# 51.net
KiCad netlist of a schematic drawn in EasyEDA Pro
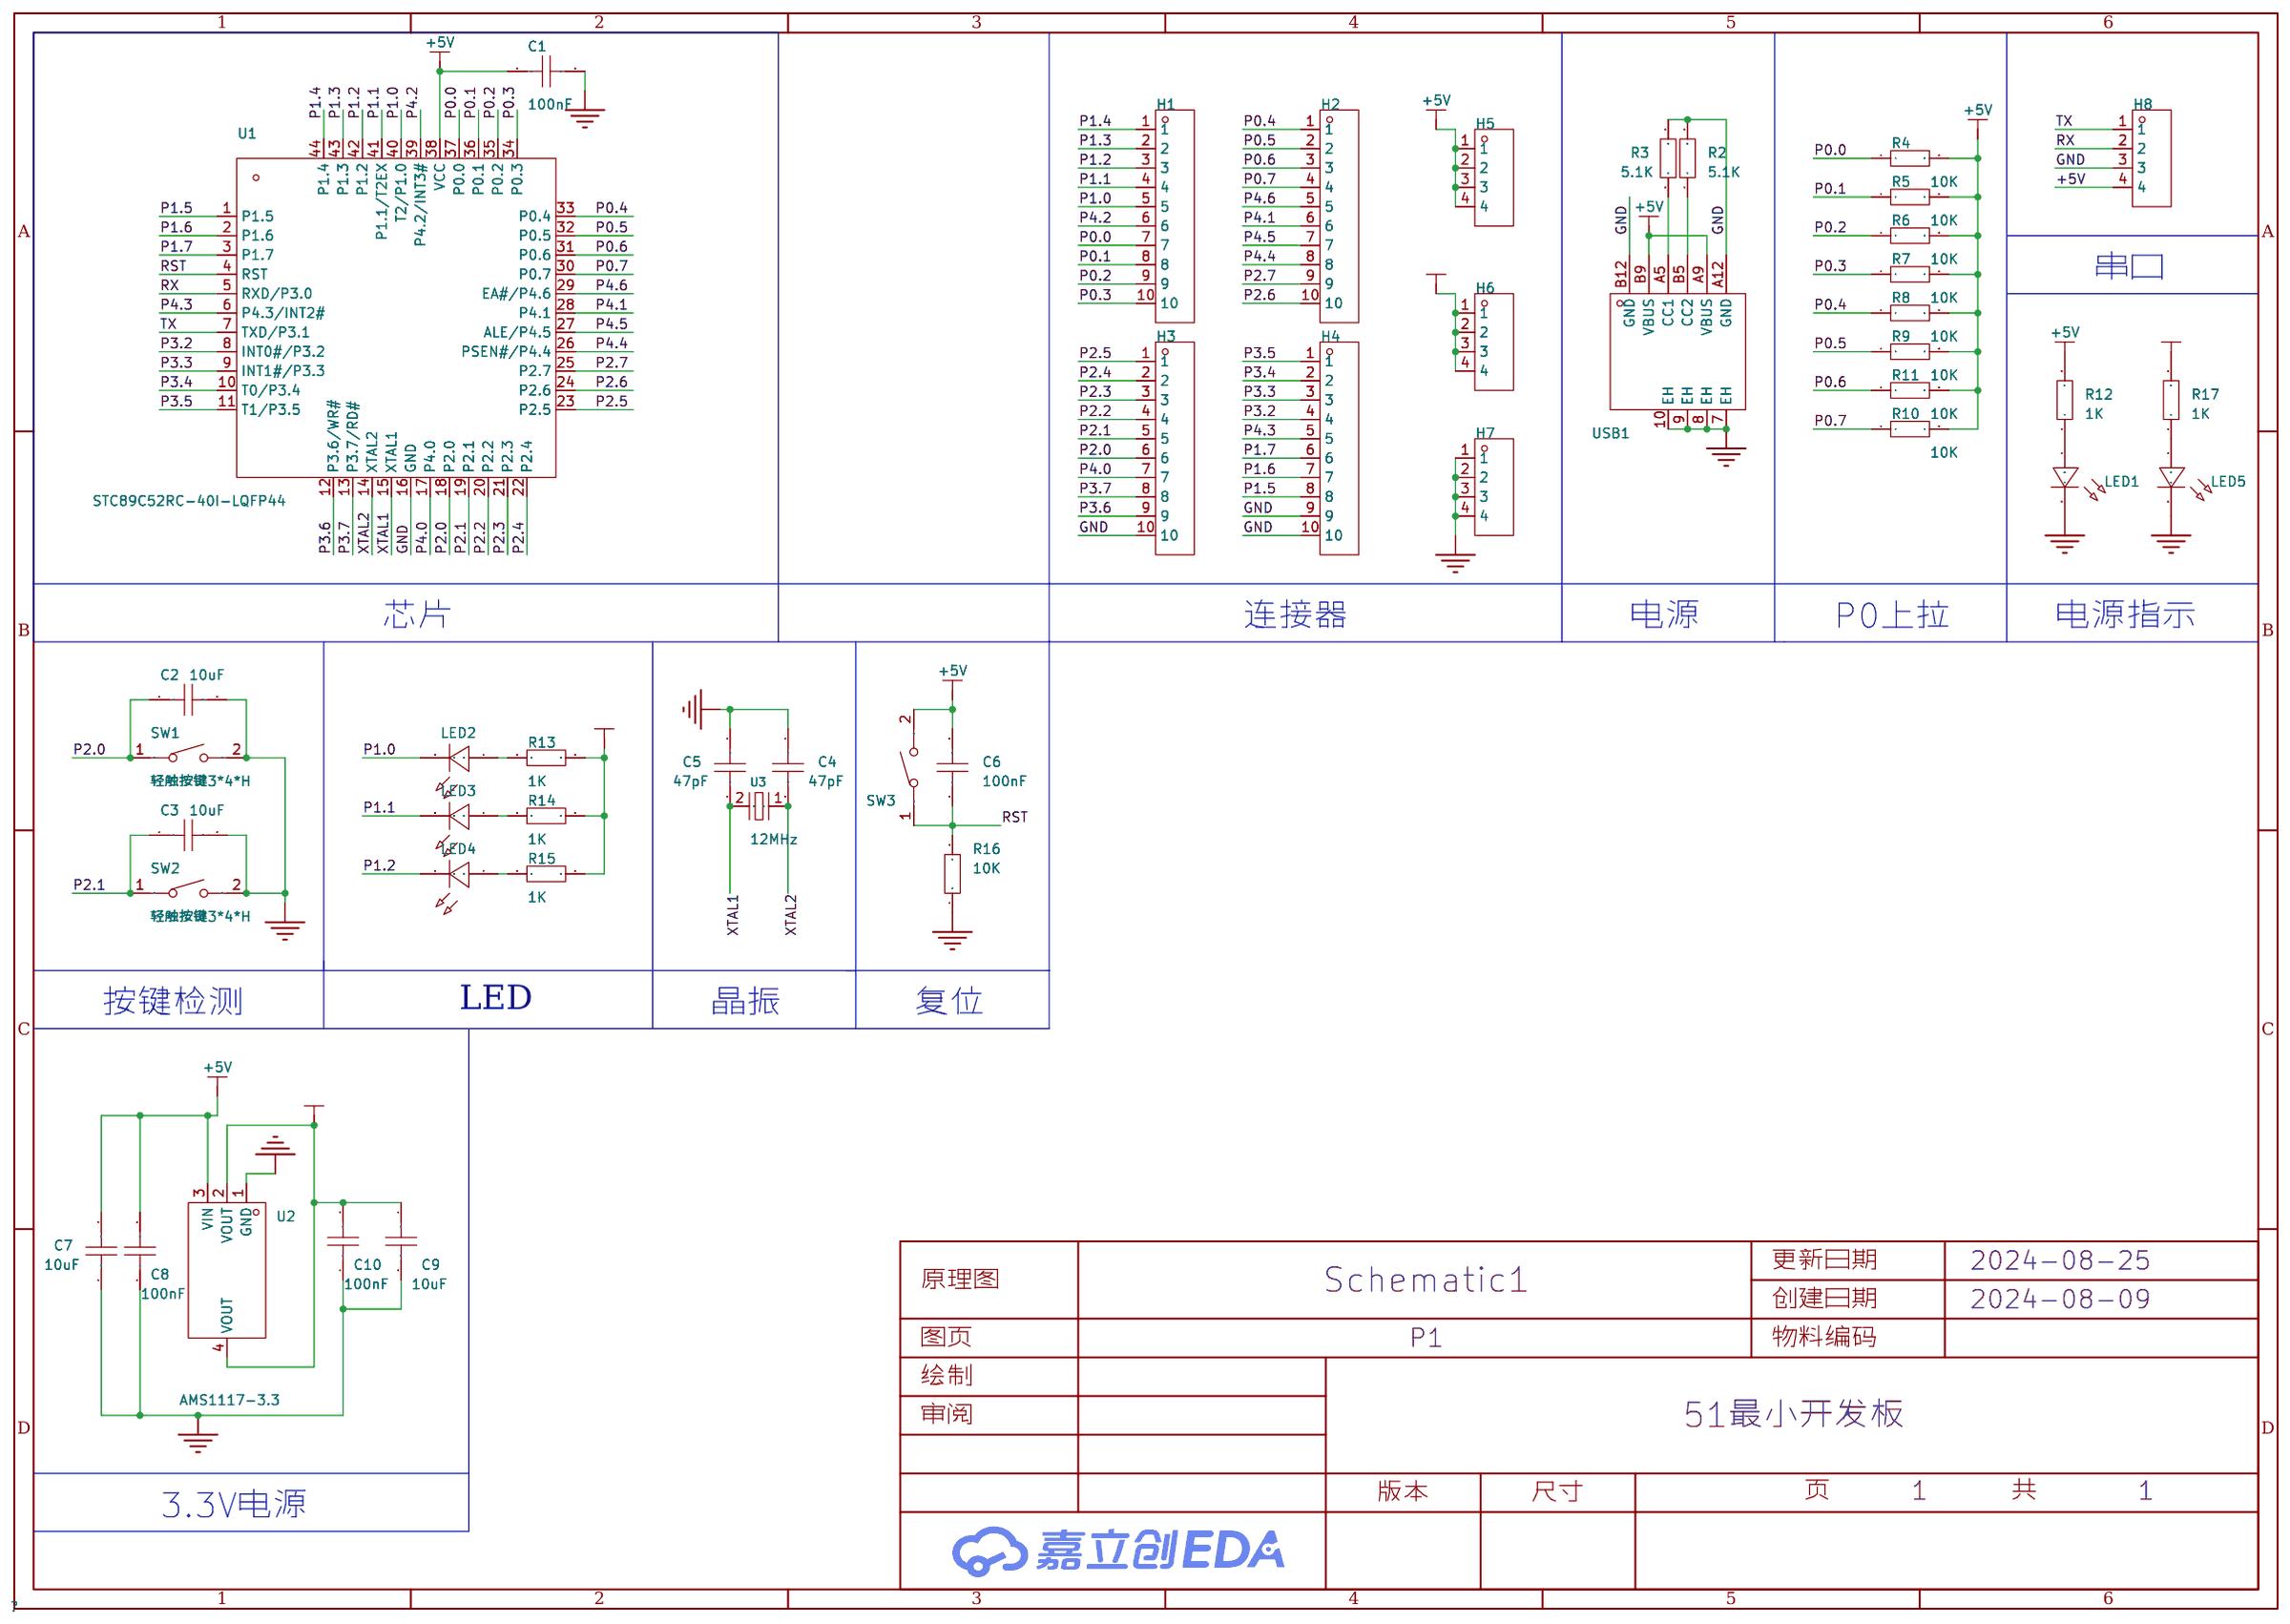
[diagram p0: schematic sheet]

(export (version "E")
  (design (tool "Eeschema 10.0.6"))
  (components
    (comp (ref "C1")
      (value "100nF")
      (footprint "easyedapro:C0603")
      (libsource (lib "easyedapro") (part "CapAcitance"))
    )
    (comp (ref "C2")
      (value "10uF")
      (footprint "easyedapro:C0603")
      (libsource (lib "easyedapro") (part "CapAcitance"))
    )
    (comp (ref "C3")
      (value "10uF")
      (footprint "easyedapro:C0603")
      (libsource (lib "easyedapro") (part "CapAcitance"))
    )
    (comp (ref "C4")
      (value "47pF")
      (footprint "easyedapro:C0603")
      (libsource (lib "easyedapro") (part "CapAcitance"))
    )
    (comp (ref "C5")
      (value "47pF")
      (footprint "easyedapro:C0603")
      (libsource (lib "easyedapro") (part "CapAcitance"))
    )
    (comp (ref "C6")
      (value "100nF")
      (footprint "easyedapro:C0603")
      (libsource (lib "easyedapro") (part "CapAcitance"))
    )
    (comp (ref "C7")
      (value "10uF")
      (footprint "easyedapro:C0603")
      (libsource (lib "easyedapro") (part "CapAcitance"))
    )
    (comp (ref "C8")
      (value "100nF")
      (footprint "easyedapro:C0603")
      (libsource (lib "easyedapro") (part "CapAcitance"))
    )
    (comp (ref "C9")
      (value "10uF")
      (footprint "easyedapro:C0603")
      (libsource (lib "easyedapro") (part "CapAcitance"))
    )
    (comp (ref "C10")
      (value "100nF")
      (footprint "easyedapro:C0603")
      (libsource (lib "easyedapro") (part "CapAcitance"))
    )
    (comp (ref "H1")
      (value "~")
      (footprint "easyedapro:HDR-TH_10P-P2.54-V-F")
      (libsource (lib "easyedapro") (part "X5511FV-10-C70D30-1000"))
    )
    (comp (ref "H2")
      (value "~")
      (footprint "easyedapro:HDR-TH_10P-P2.54-V-F")
      (libsource (lib "easyedapro") (part "X5511FV-10-C70D30-1000"))
    )
    (comp (ref "H3")
      (value "~")
      (footprint "easyedapro:HDR-TH_10P-P2.54-V-F")
      (libsource (lib "easyedapro") (part "X5511FV-10-C70D30-1000"))
    )
    (comp (ref "H4")
      (value "~")
      (footprint "easyedapro:HDR-TH_10P-P2.54-V-F")
      (libsource (lib "easyedapro") (part "X5511FV-10-C70D30-1000"))
    )
    (comp (ref "H5")
      (value "~")
      (footprint "easyedapro:HDR-TH_4P-P2.54-V-F")
      (libsource (lib "easyedapro") (part "2.54-1*4P母"))
    )
    (comp (ref "H6")
      (value "~")
      (footprint "easyedapro:HDR-TH_4P-P2.54-V-F")
      (libsource (lib "easyedapro") (part "2.54-1*4P母"))
    )
    (comp (ref "H7")
      (value "~")
      (footprint "easyedapro:HDR-TH_4P-P2.54-V-F")
      (libsource (lib "easyedapro") (part "2.54-1*4P母"))
    )
    (comp (ref "H8")
      (value "~")
      (footprint "easyedapro:HDR-TH_4P-P2.54-V-M")
      (libsource (lib "easyedapro") (part "PZ254V-11-04P"))
    )
    (comp (ref "LED1")
      (value "~")
      (footprint "easyedapro:LED_TH-3mm")
      (libsource (lib "easyedapro") (part "LED_TH-R"))
    )
    (comp (ref "LED2")
      (value "~")
      (footprint "easyedapro:LED_TH-3mm")
      (libsource (lib "easyedapro") (part "LED_TH-R"))
    )
    (comp (ref "LED3")
      (value "~")
      (footprint "easyedapro:LED_TH-3mm")
      (libsource (lib "easyedapro") (part "LED_TH-R"))
    )
    (comp (ref "LED4")
      (value "~")
      (footprint "easyedapro:LED_TH-3mm")
      (libsource (lib "easyedapro") (part "LED_TH-R"))
    )
    (comp (ref "LED5")
      (value "~")
      (footprint "easyedapro:LED_TH-3mm")
      (libsource (lib "easyedapro") (part "LED_TH-R"))
    )
    (comp (ref "R2") (value "5.1K") (footprint "easyedapro:R0603") (libsource (lib "easyedapro") (part "电阻")))
    (comp (ref "R3") (value "5.1K") (footprint "easyedapro:R0603") (libsource (lib "easyedapro") (part "电阻")))
    (comp (ref "R4") (value "10K") (footprint "easyedapro:R0603") (libsource (lib "easyedapro") (part "电阻")))
    (comp (ref "R5") (value "10K") (footprint "easyedapro:R0603") (libsource (lib "easyedapro") (part "电阻")))
    (comp (ref "R6") (value "10K") (footprint "easyedapro:R0603") (libsource (lib "easyedapro") (part "电阻")))
    (comp (ref "R7") (value "10K") (footprint "easyedapro:R0603") (libsource (lib "easyedapro") (part "电阻")))
    (comp (ref "R8") (value "10K") (footprint "easyedapro:R0603") (libsource (lib "easyedapro") (part "电阻")))
    (comp (ref "R9") (value "10K") (footprint "easyedapro:R0603") (libsource (lib "easyedapro") (part "电阻")))
    (comp (ref "R10") (value "10K") (footprint "easyedapro:R0603") (libsource (lib "easyedapro") (part "电阻")))
    (comp (ref "R11") (value "10K") (footprint "easyedapro:R0603") (libsource (lib "easyedapro") (part "电阻")))
    (comp (ref "R12") (value "1K") (footprint "easyedapro:R0603") (libsource (lib "easyedapro") (part "电阻")))
    (comp (ref "R13") (value "1K") (footprint "easyedapro:R0603") (libsource (lib "easyedapro") (part "电阻")))
    (comp (ref "R14") (value "1K") (footprint "easyedapro:R0603") (libsource (lib "easyedapro") (part "电阻")))
    (comp (ref "R15") (value "1K") (footprint "easyedapro:R0603") (libsource (lib "easyedapro") (part "电阻")))
    (comp (ref "R16") (value "10K") (footprint "easyedapro:R0603") (libsource (lib "easyedapro") (part "电阻")))
    (comp (ref "R17") (value "1K") (footprint "easyedapro:R0603") (libsource (lib "easyedapro") (part "电阻")))
    (comp (ref "SW1")
      (value "轻触按键3*4*H")
      (footprint "easyedapro:SW-SMD_L4.0-W2.9-LS5.0")
      (libsource (lib "easyedapro") (part "轻触按键3*4*H"))
    )
    (comp (ref "SW2")
      (value "轻触按键3*4*H")
      (footprint "easyedapro:SW-SMD_L4.0-W2.9-LS5.0")
      (libsource (lib "easyedapro") (part "轻触按键3*4*H"))
    )
    (comp (ref "SW3")
      (value "轻触按键3*4*H")
      (footprint "easyedapro:SW-SMD_L4.0-W2.9-LS5.0")
      (libsource (lib "easyedapro") (part "轻触按键3*4*H"))
    )
    (comp (ref "U1")
      (value "STC89C52RC-40I-LQFP44")
      (footprint "easyedapro:LQFP-44_L10.0-W10.0-P0.80-LS12.0-BL")
      (description "CPU内核:51系列;程序存储容量:8KB;RAM总容量:512Byte;GPIO端口数量:39;工作电压范围:3.3V~5.5V;CPU最大主频:-;程序存储器类型:FLASH;")
      (fields (field (name "Manufacturer") "STC(宏晶)"))
      (libsource (lib "easyedapro") (part "STC89C52RC-40I_C8707"))
    )
    (comp (ref "U2")
      (value "AMS1117-3.3")
      (footprint "easyedapro:SOT-223-3_L6.5-W3.4-P2.30-LS7.0-BR")
      (description "输出类型:固定;最大输入电压:-;输出电压:3.3V;最大输出电流:1A;电源纹波抑制比(PSRR):72dB@(120Hz);输出极性:正极;")
      (fields (field (name "Manufacturer") "AMS"))
      (libsource (lib "easyedapro") (part "AMS1117-3.3"))
    )
    (comp (ref "U3")
      (value "12MHz")
      (footprint "easyedapro:CRYSTAL-SMD_L11.4-W4.7-LS12.7")
      (description "频率:12MHz;常温频差:±30ppm;外接负载电容:18pF;频率稳定度(全温):±35ppm;")
      (fields
        (field (name "Manufacturer Part") "ABLS-12.000MHZ-B4H-T")
        (field (name "Manufacturer") "ABRACON")
      )
      (libsource (lib "easyedapro") (part "ABLS-12.000MHZ-B4H-T"))
    )
    (comp (ref "USB1")
      (value "~")
      (footprint "easyedapro:USB_ TYPE-C-6P")
      (libsource (lib "easyedapro") (part "USB_ TYPE-C-6P"))
    )
  )
  (nets
    (net (code "1") (name "+5V") (class "Default")
      (node (ref "C1") (pin "1") (pinfunction "1_1") (pintype "input"))
      (node (ref "C6") (pin "2") (pinfunction "2_2") (pintype "input"))
      (node (ref "C7") (pin "1") (pinfunction "1_1") (pintype "input"))
      (node (ref "C8") (pin "2") (pinfunction "2_2") (pintype "input"))
      (node (ref "H5") (pin "1") (pinfunction "1_1") (pintype "unspecified"))
      (node (ref "H5") (pin "2") (pinfunction "2_2") (pintype "unspecified"))
      (node (ref "H5") (pin "3") (pinfunction "3_3") (pintype "unspecified"))
      (node (ref "H5") (pin "4") (pinfunction "4_4") (pintype "unspecified"))
      (node (ref "H8") (pin "4") (pinfunction "4_4") (pintype "unspecified"))
      (node (ref "R10") (pin "2") (pinfunction "2_2") (pintype "input"))
      (node (ref "R11") (pin "2") (pinfunction "2_2") (pintype "input"))
      (node (ref "R12") (pin "2") (pinfunction "2_2") (pintype "input"))
      (node (ref "R4") (pin "2") (pinfunction "2_2") (pintype "input"))
      (node (ref "R5") (pin "2") (pinfunction "2_2") (pintype "input"))
      (node (ref "R6") (pin "2") (pinfunction "2_2") (pintype "input"))
      (node (ref "R7") (pin "2") (pinfunction "2_2") (pintype "input"))
      (node (ref "R8") (pin "2") (pinfunction "2_2") (pintype "input"))
      (node (ref "R9") (pin "2") (pinfunction "2_2") (pintype "input"))
      (node (ref "SW3") (pin "2") (pinfunction "2_2") (pintype "unspecified"))
      (node (ref "U1") (pin "38") (pinfunction "VCC_38") (pintype "unspecified"))
      (node (ref "U2") (pin "3") (pinfunction "VIN_3") (pintype "unspecified"))
      (node (ref "USB1") (pin "A9") (pinfunction "VBUS_A9") (pintype "input"))
      (node (ref "USB1") (pin "B9") (pinfunction "VBUS_B9") (pintype "input"))
    )
    (net (code "2") (name "/P0.0") (class "Default")
      (node (ref "H1") (pin "7") (pinfunction "7_7") (pintype "unspecified"))
      (node (ref "R4") (pin "1") (pinfunction "1_1") (pintype "input"))
      (node (ref "U1") (pin "37") (pinfunction "P0.0_37") (pintype "unspecified"))
    )
    (net (code "3") (name "/P0.1") (class "Default")
      (node (ref "H1") (pin "8") (pinfunction "8_8") (pintype "unspecified"))
      (node (ref "R5") (pin "1") (pinfunction "1_1") (pintype "input"))
      (node (ref "U1") (pin "36") (pinfunction "P0.1_36") (pintype "unspecified"))
    )
    (net (code "4") (name "/P0.2") (class "Default")
      (node (ref "H1") (pin "9") (pinfunction "9_9") (pintype "unspecified"))
      (node (ref "R6") (pin "1") (pinfunction "1_1") (pintype "input"))
      (node (ref "U1") (pin "35") (pinfunction "P0.2_35") (pintype "unspecified"))
    )
    (net (code "5") (name "/P0.3") (class "Default")
      (node (ref "H1") (pin "10") (pinfunction "10_10") (pintype "unspecified"))
      (node (ref "R7") (pin "1") (pinfunction "1_1") (pintype "input"))
      (node (ref "U1") (pin "34") (pinfunction "P0.3_34") (pintype "unspecified"))
    )
    (net (code "6") (name "/P0.4") (class "Default")
      (node (ref "H2") (pin "1") (pinfunction "1_1") (pintype "unspecified"))
      (node (ref "R8") (pin "1") (pinfunction "1_1") (pintype "input"))
      (node (ref "U1") (pin "33") (pinfunction "P0.4_33") (pintype "unspecified"))
    )
    (net (code "7") (name "/P0.5") (class "Default")
      (node (ref "H2") (pin "2") (pinfunction "2_2") (pintype "unspecified"))
      (node (ref "R9") (pin "1") (pinfunction "1_1") (pintype "input"))
      (node (ref "U1") (pin "32") (pinfunction "P0.5_32") (pintype "unspecified"))
    )
    (net (code "8") (name "/P0.6") (class "Default")
      (node (ref "H2") (pin "3") (pinfunction "3_3") (pintype "unspecified"))
      (node (ref "R11") (pin "1") (pinfunction "1_1") (pintype "input"))
      (node (ref "U1") (pin "31") (pinfunction "P0.6_31") (pintype "unspecified"))
    )
    (net (code "9") (name "/P0.7") (class "Default")
      (node (ref "H2") (pin "4") (pinfunction "4_4") (pintype "unspecified"))
      (node (ref "R10") (pin "1") (pinfunction "1_1") (pintype "input"))
      (node (ref "U1") (pin "30") (pinfunction "P0.7_30") (pintype "unspecified"))
    )
    (net (code "10") (name "/P1.0") (class "Default")
      (node (ref "H1") (pin "5") (pinfunction "5_5") (pintype "unspecified"))
      (node (ref "LED2") (pin "2") (pinfunction "A_2") (pintype "input"))
      (node (ref "U1") (pin "40") (pinfunction "T2/P1.0_40") (pintype "unspecified"))
    )
    (net (code "11") (name "/P1.1") (class "Default")
      (node (ref "H1") (pin "4") (pinfunction "4_4") (pintype "unspecified"))
      (node (ref "LED3") (pin "2") (pinfunction "A_2") (pintype "input"))
      (node (ref "U1") (pin "41") (pinfunction "P1.1/T2EX_41") (pintype "unspecified"))
    )
    (net (code "12") (name "/P1.2") (class "Default")
      (node (ref "H1") (pin "3") (pinfunction "3_3") (pintype "unspecified"))
      (node (ref "LED4") (pin "2") (pinfunction "A_2") (pintype "input"))
      (node (ref "U1") (pin "42") (pinfunction "P1.2_42") (pintype "unspecified"))
    )
    (net (code "13") (name "/P1.3") (class "Default")
      (node (ref "H1") (pin "2") (pinfunction "2_2") (pintype "unspecified"))
      (node (ref "U1") (pin "43") (pinfunction "P1.3_43") (pintype "unspecified"))
    )
    (net (code "14") (name "/P1.4") (class "Default")
      (node (ref "H1") (pin "1") (pinfunction "1_1") (pintype "unspecified"))
      (node (ref "U1") (pin "44") (pinfunction "P1.4_44") (pintype "unspecified"))
    )
    (net (code "15") (name "/P1.5") (class "Default")
      (node (ref "H4") (pin "8") (pinfunction "8_8") (pintype "unspecified"))
      (node (ref "U1") (pin "1") (pinfunction "P1.5_1") (pintype "unspecified"))
    )
    (net (code "16") (name "/P1.6") (class "Default")
      (node (ref "H4") (pin "7") (pinfunction "7_7") (pintype "unspecified"))
      (node (ref "U1") (pin "2") (pinfunction "P1.6_2") (pintype "unspecified"))
    )
    (net (code "17") (name "/P1.7") (class "Default")
      (node (ref "H4") (pin "6") (pinfunction "6_6") (pintype "unspecified"))
      (node (ref "U1") (pin "3") (pinfunction "P1.7_3") (pintype "unspecified"))
    )
    (net (code "18") (name "/P2.0") (class "Default")
      (node (ref "C2") (pin "1") (pinfunction "1_1") (pintype "input"))
      (node (ref "H3") (pin "6") (pinfunction "6_6") (pintype "unspecified"))
      (node (ref "SW1") (pin "1") (pinfunction "1_1") (pintype "unspecified"))
      (node (ref "U1") (pin "18") (pinfunction "P2.0_18") (pintype "unspecified"))
    )
    (net (code "19") (name "/P2.1") (class "Default")
      (node (ref "C3") (pin "1") (pinfunction "1_1") (pintype "input"))
      (node (ref "H3") (pin "5") (pinfunction "5_5") (pintype "unspecified"))
      (node (ref "SW2") (pin "1") (pinfunction "1_1") (pintype "unspecified"))
      (node (ref "U1") (pin "19") (pinfunction "P2.1_19") (pintype "unspecified"))
    )
    (net (code "20") (name "/P2.2") (class "Default")
      (node (ref "H3") (pin "4") (pinfunction "4_4") (pintype "unspecified"))
      (node (ref "U1") (pin "20") (pinfunction "P2.2_20") (pintype "unspecified"))
    )
    (net (code "21") (name "/P2.3") (class "Default")
      (node (ref "H3") (pin "3") (pinfunction "3_3") (pintype "unspecified"))
      (node (ref "U1") (pin "21") (pinfunction "P2.3_21") (pintype "unspecified"))
    )
    (net (code "22") (name "/P2.4") (class "Default")
      (node (ref "H3") (pin "2") (pinfunction "2_2") (pintype "unspecified"))
      (node (ref "U1") (pin "22") (pinfunction "P2.4_22") (pintype "unspecified"))
    )
    (net (code "23") (name "/P2.5") (class "Default")
      (node (ref "H3") (pin "1") (pinfunction "1_1") (pintype "unspecified"))
      (node (ref "U1") (pin "23") (pinfunction "P2.5_23") (pintype "unspecified"))
    )
    (net (code "24") (name "/P2.6") (class "Default")
      (node (ref "H2") (pin "10") (pinfunction "10_10") (pintype "unspecified"))
      (node (ref "U1") (pin "24") (pinfunction "P2.6_24") (pintype "unspecified"))
    )
    (net (code "25") (name "/P2.7") (class "Default")
      (node (ref "H2") (pin "9") (pinfunction "9_9") (pintype "unspecified"))
      (node (ref "U1") (pin "25") (pinfunction "P2.7_25") (pintype "unspecified"))
    )
    (net (code "26") (name "/P3.2") (class "Default")
      (node (ref "H4") (pin "4") (pinfunction "4_4") (pintype "unspecified"))
      (node (ref "U1") (pin "8") (pinfunction "INT0#/P3.2_8") (pintype "unspecified"))
    )
    (net (code "27") (name "/P3.3") (class "Default")
      (node (ref "H4") (pin "3") (pinfunction "3_3") (pintype "unspecified"))
      (node (ref "U1") (pin "9") (pinfunction "INT1#/P3.3_9") (pintype "unspecified"))
    )
    (net (code "28") (name "/P3.4") (class "Default")
      (node (ref "H4") (pin "2") (pinfunction "2_2") (pintype "unspecified"))
      (node (ref "U1") (pin "10") (pinfunction "T0/P3.4_10") (pintype "unspecified"))
    )
    (net (code "29") (name "/P3.5") (class "Default")
      (node (ref "H4") (pin "1") (pinfunction "1_1") (pintype "unspecified"))
      (node (ref "U1") (pin "11") (pinfunction "T1/P3.5_11") (pintype "unspecified"))
    )
    (net (code "30") (name "/P3.6") (class "Default")
      (node (ref "H3") (pin "9") (pinfunction "9_9") (pintype "unspecified"))
      (node (ref "U1") (pin "12") (pinfunction "P3.6/WR#_12") (pintype "unspecified"))
    )
    (net (code "31") (name "/P3.7") (class "Default")
      (node (ref "H3") (pin "8") (pinfunction "8_8") (pintype "unspecified"))
      (node (ref "U1") (pin "13") (pinfunction "P3.7/RD#_13") (pintype "unspecified"))
    )
    (net (code "32") (name "/P4.0") (class "Default")
      (node (ref "H3") (pin "7") (pinfunction "7_7") (pintype "unspecified"))
      (node (ref "U1") (pin "17") (pinfunction "P4.0_17") (pintype "unspecified"))
    )
    (net (code "33") (name "/P4.1") (class "Default")
      (node (ref "H2") (pin "6") (pinfunction "6_6") (pintype "unspecified"))
      (node (ref "U1") (pin "28") (pinfunction "P4.1_28") (pintype "unspecified"))
    )
    (net (code "34") (name "/P4.2") (class "Default")
      (node (ref "H1") (pin "6") (pinfunction "6_6") (pintype "unspecified"))
      (node (ref "U1") (pin "39") (pinfunction "P4.2/INT3#_39") (pintype "unspecified"))
    )
    (net (code "35") (name "/P4.3") (class "Default")
      (node (ref "H4") (pin "5") (pinfunction "5_5") (pintype "unspecified"))
      (node (ref "U1") (pin "6") (pinfunction "P4.3/INT2#_6") (pintype "unspecified"))
    )
    (net (code "36") (name "/P4.4") (class "Default")
      (node (ref "H2") (pin "8") (pinfunction "8_8") (pintype "unspecified"))
      (node (ref "U1") (pin "26") (pinfunction "PSEN#/P4.4_26") (pintype "unspecified"))
    )
    (net (code "37") (name "/P4.5") (class "Default")
      (node (ref "H2") (pin "7") (pinfunction "7_7") (pintype "unspecified"))
      (node (ref "U1") (pin "27") (pinfunction "ALE/P4.5_27") (pintype "unspecified"))
    )
    (net (code "38") (name "/P4.6") (class "Default")
      (node (ref "H2") (pin "5") (pinfunction "5_5") (pintype "unspecified"))
      (node (ref "U1") (pin "29") (pinfunction "EA#/P4.6_29") (pintype "unspecified"))
    )
    (net (code "39") (name "/RST") (class "Default")
      (node (ref "C6") (pin "1") (pinfunction "1_1") (pintype "input"))
      (node (ref "R16") (pin "2") (pinfunction "2_2") (pintype "input"))
      (node (ref "SW3") (pin "1") (pinfunction "1_1") (pintype "unspecified"))
      (node (ref "U1") (pin "4") (pinfunction "RST_4") (pintype "unspecified"))
    )
    (net (code "40") (name "/RX") (class "Default")
      (node (ref "H8") (pin "2") (pinfunction "2_2") (pintype "unspecified"))
      (node (ref "U1") (pin "5") (pinfunction "RXD/P3.0_5") (pintype "unspecified"))
    )
    (net (code "41") (name "/TX") (class "Default")
      (node (ref "H8") (pin "1") (pinfunction "1_1") (pintype "unspecified"))
      (node (ref "U1") (pin "7") (pinfunction "TXD/P3.1_7") (pintype "unspecified"))
    )
    (net (code "42") (name "/XTAL1") (class "Default")
      (node (ref "C5") (pin "2") (pinfunction "2_2") (pintype "input"))
      (node (ref "U1") (pin "15") (pinfunction "XTAL1_15") (pintype "unspecified"))
      (node (ref "U3") (pin "2") (pinfunction "GND_2") (pintype "input"))
    )
    (net (code "43") (name "/XTAL2") (class "Default")
      (node (ref "C4") (pin "2") (pinfunction "2_2") (pintype "input"))
      (node (ref "U1") (pin "14") (pinfunction "XTAL2_14") (pintype "unspecified"))
      (node (ref "U3") (pin "1") (pinfunction "1_1") (pintype "input"))
    )
    (net (code "44") (name "GND") (class "Default")
      (node (ref "C1") (pin "2") (pinfunction "2_2") (pintype "input"))
      (node (ref "C10") (pin "1") (pinfunction "1_1") (pintype "input"))
      (node (ref "C2") (pin "2") (pinfunction "2_2") (pintype "input"))
      (node (ref "C3") (pin "2") (pinfunction "2_2") (pintype "input"))
      (node (ref "C4") (pin "1") (pinfunction "1_1") (pintype "input"))
      (node (ref "C5") (pin "1") (pinfunction "1_1") (pintype "input"))
      (node (ref "C7") (pin "2") (pinfunction "2_2") (pintype "input"))
      (node (ref "C8") (pin "1") (pinfunction "1_1") (pintype "input"))
      (node (ref "C9") (pin "2") (pinfunction "2_2") (pintype "input"))
      (node (ref "H3") (pin "10") (pinfunction "10_10") (pintype "unspecified"))
      (node (ref "H4") (pin "10") (pinfunction "10_10") (pintype "unspecified"))
      (node (ref "H4") (pin "9") (pinfunction "9_9") (pintype "unspecified"))
      (node (ref "H7") (pin "1") (pinfunction "1_1") (pintype "unspecified"))
      (node (ref "H7") (pin "2") (pinfunction "2_2") (pintype "unspecified"))
      (node (ref "H7") (pin "3") (pinfunction "3_3") (pintype "unspecified"))
      (node (ref "H7") (pin "4") (pinfunction "4_4") (pintype "unspecified"))
      (node (ref "H8") (pin "3") (pinfunction "3_3") (pintype "unspecified"))
      (node (ref "LED1") (pin "2") (pinfunction "A_2") (pintype "input"))
      (node (ref "LED5") (pin "2") (pinfunction "A_2") (pintype "input"))
      (node (ref "R16") (pin "1") (pinfunction "1_1") (pintype "input"))
      (node (ref "R2") (pin "2") (pinfunction "2_2") (pintype "input"))
      (node (ref "R3") (pin "2") (pinfunction "2_2") (pintype "input"))
      (node (ref "SW1") (pin "2") (pinfunction "2_2") (pintype "unspecified"))
      (node (ref "SW2") (pin "2") (pinfunction "2_2") (pintype "unspecified"))
      (node (ref "U1") (pin "16") (pinfunction "GND_16") (pintype "unspecified"))
      (node (ref "U2") (pin "1") (pinfunction "GND_1") (pintype "unspecified"))
      (node (ref "USB1") (pin "10") (pinfunction "EH_10") (pintype "input"))
      (node (ref "USB1") (pin "7") (pinfunction "EH_7") (pintype "input"))
      (node (ref "USB1") (pin "8") (pinfunction "EH_8") (pintype "input"))
      (node (ref "USB1") (pin "9") (pinfunction "EH_9") (pintype "input"))
      (node (ref "USB1") (pin "A12") (pinfunction "GND_A12") (pintype "input"))
      (node (ref "USB1") (pin "B12") (pinfunction "GND_B12") (pintype "input"))
    )
    (net (code "45") (name "Net-(LED1-C)") (class "Default")
      (node (ref "LED1") (pin "1") (pinfunction "C_1") (pintype "input"))
      (node (ref "R12") (pin "1") (pinfunction "1_1") (pintype "input"))
    )
    (net (code "46") (name "Net-(LED2-C)") (class "Default")
      (node (ref "LED2") (pin "1") (pinfunction "C_1") (pintype "input"))
      (node (ref "R13") (pin "1") (pinfunction "1_1") (pintype "input"))
    )
    (net (code "47") (name "Net-(LED3-C)") (class "Default")
      (node (ref "LED3") (pin "1") (pinfunction "C_1") (pintype "input"))
      (node (ref "R14") (pin "1") (pinfunction "1_1") (pintype "input"))
    )
    (net (code "48") (name "Net-(LED4-C)") (class "Default")
      (node (ref "LED4") (pin "1") (pinfunction "C_1") (pintype "input"))
      (node (ref "R15") (pin "1") (pinfunction "1_1") (pintype "input"))
    )
    (net (code "49") (name "Net-(LED5-C)") (class "Default")
      (node (ref "LED5") (pin "1") (pinfunction "C_1") (pintype "input"))
      (node (ref "R17") (pin "1") (pinfunction "1_1") (pintype "input"))
    )
    (net (code "50") (name "Net-(USB1-CC1)") (class "Default")
      (node (ref "R3") (pin "1") (pinfunction "1_1") (pintype "input"))
      (node (ref "USB1") (pin "A5") (pinfunction "CC1_A5") (pintype "input"))
    )
    (net (code "51") (name "Net-(USB1-CC2)") (class "Default")
      (node (ref "R2") (pin "1") (pinfunction "1_1") (pintype "input"))
      (node (ref "USB1") (pin "B5") (pinfunction "CC2_B5") (pintype "input"))
    )
    (net (code "52") (name "VCC_3.3") (class "Default")
      (node (ref "C10") (pin "2") (pinfunction "2_2") (pintype "input"))
      (node (ref "C9") (pin "1") (pinfunction "1_1") (pintype "input"))
      (node (ref "H6") (pin "1") (pinfunction "1_1") (pintype "unspecified"))
      (node (ref "H6") (pin "2") (pinfunction "2_2") (pintype "unspecified"))
      (node (ref "H6") (pin "3") (pinfunction "3_3") (pintype "unspecified"))
      (node (ref "H6") (pin "4") (pinfunction "4_4") (pintype "unspecified"))
      (node (ref "R13") (pin "2") (pinfunction "2_2") (pintype "input"))
      (node (ref "R14") (pin "2") (pinfunction "2_2") (pintype "input"))
      (node (ref "R15") (pin "2") (pinfunction "2_2") (pintype "input"))
      (node (ref "R17") (pin "2") (pinfunction "2_2") (pintype "input"))
      (node (ref "U2") (pin "2") (pinfunction "VOUT_2") (pintype "unspecified"))
      (node (ref "U2") (pin "4") (pinfunction "VOUT_4") (pintype "unspecified"))
    )
  )
)
